# Trigger_And_Clock_Muxing.net
KiCad netlist of a schematic drawn in Altium Designer
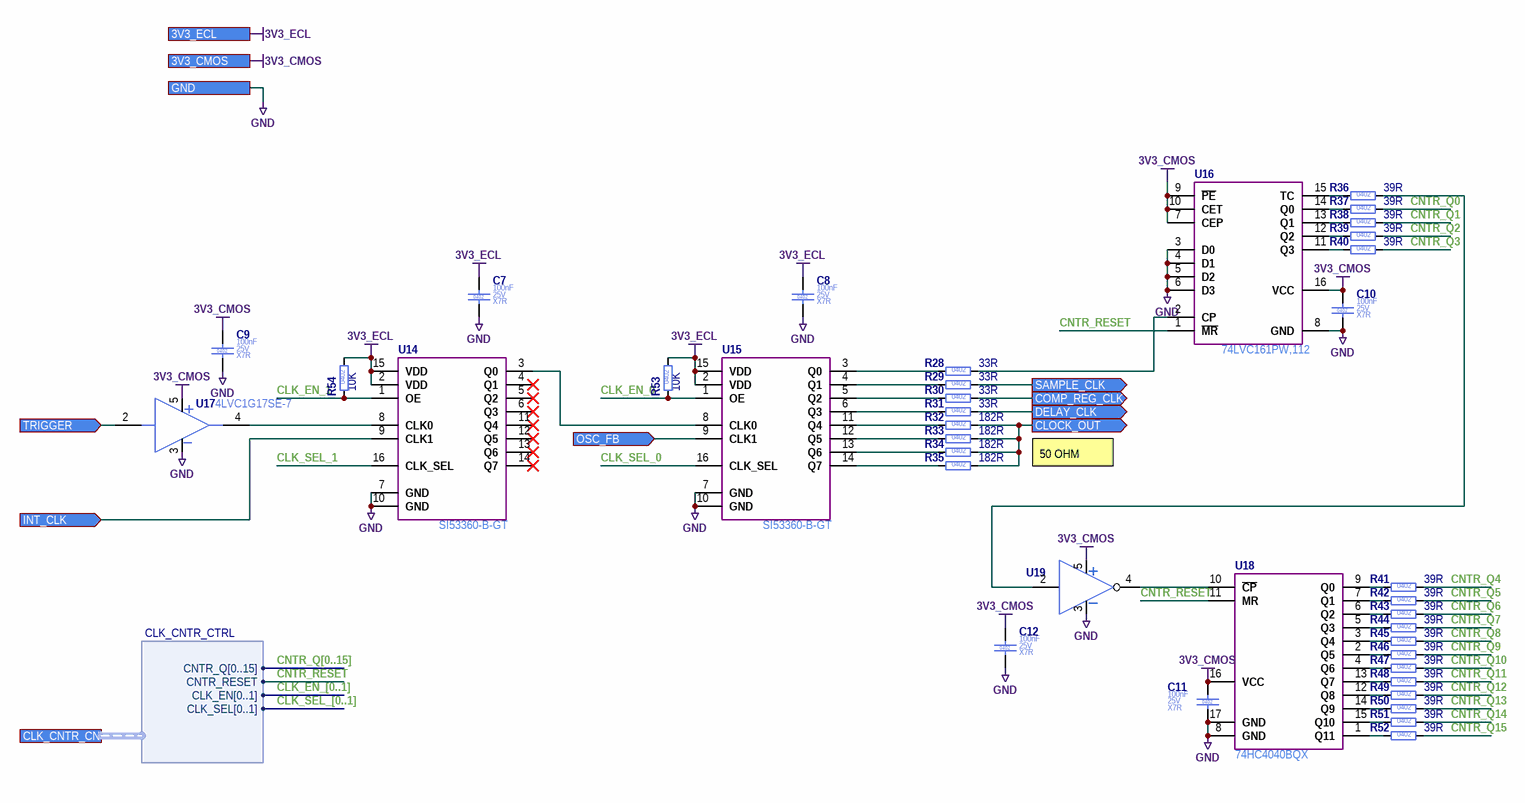
[diagram p0: Trigger_And_Clock_Muxing.SchDoc]

(export (version "E")
  (design (tool "Eeschema 10.0.6"))
  (components
    (comp (ref "C7")
      (value "C_100NF_25V_X7R_0402_10")
      (footprint "C_0402_1005")
      (description "Ceramic Capacitor")
      (fields
        (field (name "CASE/PACKAGE") "0402")
        (field (name "VOLTAGE RATING (DC)") "25V")
        (field (name "DIELECTRIC") "X7R")
        (field (name "CAPACITANCE") "100nF")
        (field (name "TOLERANCE") "10%")
        (field (name "MANUFACTURER PART NUMBER") "EMK105B7104KV-F")
      )
      (libsource (lib "7Sigma") (part "C"))
    )
    (comp (ref "C8")
      (value "C_100NF_25V_X7R_0402_10")
      (footprint "C_0402_1005")
      (description "Ceramic Capacitor")
      (fields
        (field (name "CASE/PACKAGE") "0402")
        (field (name "VOLTAGE RATING (DC)") "25V")
        (field (name "DIELECTRIC") "X7R")
        (field (name "CAPACITANCE") "100nF")
        (field (name "TOLERANCE") "10%")
        (field (name "MANUFACTURER PART NUMBER") "EMK105B7104KV-F")
      )
      (libsource (lib "7Sigma") (part "C"))
    )
    (comp (ref "C9")
      (value "C_100NF_25V_X7R_0402_10")
      (footprint "C_0402_1005")
      (description "Ceramic Capacitor")
      (fields
        (field (name "CASE/PACKAGE") "0402")
        (field (name "VOLTAGE RATING (DC)") "25V")
        (field (name "DIELECTRIC") "X7R")
        (field (name "CAPACITANCE") "100nF")
        (field (name "TOLERANCE") "10%")
        (field (name "MANUFACTURER PART NUMBER") "EMK105B7104KV-F")
      )
      (libsource (lib "7Sigma") (part "C"))
    )
    (comp (ref "C10")
      (value "C_100NF_25V_X7R_0402_10")
      (footprint "C_0402_1005")
      (description "Ceramic Capacitor")
      (fields
        (field (name "CASE/PACKAGE") "0402")
        (field (name "VOLTAGE RATING (DC)") "25V")
        (field (name "DIELECTRIC") "X7R")
        (field (name "CAPACITANCE") "100nF")
        (field (name "TOLERANCE") "10%")
        (field (name "MANUFACTURER PART NUMBER") "EMK105B7104KV-F")
      )
      (libsource (lib "7Sigma") (part "C"))
    )
    (comp (ref "C11")
      (value "C_100NF_25V_X7R_0402_10")
      (footprint "C_0402_1005")
      (description "Ceramic Capacitor")
      (fields
        (field (name "CASE/PACKAGE") "0402")
        (field (name "VOLTAGE RATING (DC)") "25V")
        (field (name "DIELECTRIC") "X7R")
        (field (name "CAPACITANCE") "100nF")
        (field (name "TOLERANCE") "10%")
        (field (name "MANUFACTURER PART NUMBER") "EMK105B7104KV-F")
      )
      (libsource (lib "7Sigma") (part "C"))
    )
    (comp (ref "C12")
      (value "C_100NF_25V_X7R_0402_10")
      (footprint "C_0402_1005")
      (description "Ceramic Capacitor")
      (fields
        (field (name "CASE/PACKAGE") "0402")
        (field (name "VOLTAGE RATING (DC)") "25V")
        (field (name "DIELECTRIC") "X7R")
        (field (name "CAPACITANCE") "100nF")
        (field (name "TOLERANCE") "10%")
        (field (name "MANUFACTURER PART NUMBER") "EMK105B7104KV-F")
      )
      (libsource (lib "7Sigma") (part "C"))
    )
    (comp (ref "R28")
      (value "R_33R_0402_1")
      (footprint "R_0402_1005")
      (description "Thick Film Resistor")
      (fields
        (field (name "RESISTANCE") "33R")
        (field (name "CASE/PACKAGE") "0402")
        (field (name "TOLERANCE") "1%")
        (field (name "MANUFACTURER") "Yageo")
      )
      (libsource (lib "7Sigma") (part "R"))
    )
    (comp (ref "R29")
      (value "R_33R_0402_1")
      (footprint "R_0402_1005")
      (description "Thick Film Resistor")
      (fields
        (field (name "RESISTANCE") "33R")
        (field (name "CASE/PACKAGE") "0402")
        (field (name "TOLERANCE") "1%")
        (field (name "MANUFACTURER") "Yageo")
      )
      (libsource (lib "7Sigma") (part "R"))
    )
    (comp (ref "R30")
      (value "R_33R_0402_1")
      (footprint "R_0402_1005")
      (description "Thick Film Resistor")
      (fields
        (field (name "RESISTANCE") "33R")
        (field (name "CASE/PACKAGE") "0402")
        (field (name "TOLERANCE") "1%")
        (field (name "MANUFACTURER") "Yageo")
      )
      (libsource (lib "7Sigma") (part "R"))
    )
    (comp (ref "R31")
      (value "R_33R_0402_1")
      (footprint "R_0402_1005")
      (description "Thick Film Resistor")
      (fields
        (field (name "RESISTANCE") "33R")
        (field (name "CASE/PACKAGE") "0402")
        (field (name "TOLERANCE") "1%")
        (field (name "MANUFACTURER") "Yageo")
      )
      (libsource (lib "7Sigma") (part "R"))
    )
    (comp (ref "R32")
      (value "R_182R_0402_1")
      (footprint "R_0402_1005")
      (description "Thick Film Resistor")
      (fields
        (field (name "RESISTANCE") "182R")
        (field (name "CASE/PACKAGE") "0402")
        (field (name "TOLERANCE") "1%")
        (field (name "MANUFACTURER") "Yageo")
      )
      (libsource (lib "7Sigma") (part "R"))
    )
    (comp (ref "R33")
      (value "R_182R_0402_1")
      (footprint "R_0402_1005")
      (description "Thick Film Resistor")
      (fields
        (field (name "RESISTANCE") "182R")
        (field (name "CASE/PACKAGE") "0402")
        (field (name "TOLERANCE") "1%")
        (field (name "MANUFACTURER") "Yageo")
      )
      (libsource (lib "7Sigma") (part "R"))
    )
    (comp (ref "R34")
      (value "R_182R_0402_1")
      (footprint "R_0402_1005")
      (description "Thick Film Resistor")
      (fields
        (field (name "RESISTANCE") "182R")
        (field (name "CASE/PACKAGE") "0402")
        (field (name "TOLERANCE") "1%")
        (field (name "MANUFACTURER") "Yageo")
      )
      (libsource (lib "7Sigma") (part "R"))
    )
    (comp (ref "R35")
      (value "R_182R_0402_1")
      (footprint "R_0402_1005")
      (description "Thick Film Resistor")
      (fields
        (field (name "RESISTANCE") "182R")
        (field (name "CASE/PACKAGE") "0402")
        (field (name "TOLERANCE") "1%")
        (field (name "MANUFACTURER") "Yageo")
      )
      (libsource (lib "7Sigma") (part "R"))
    )
    (comp (ref "R36")
      (value "R_39R_0402_1")
      (footprint "R_0402_1005")
      (description "Thick Film Resistor")
      (fields
        (field (name "RESISTANCE") "39R")
        (field (name "CASE/PACKAGE") "0402")
        (field (name "TOLERANCE") "1%")
        (field (name "MANUFACTURER") "Yageo")
      )
      (libsource (lib "7Sigma") (part "R"))
    )
    (comp (ref "R37")
      (value "R_39R_0402_1")
      (footprint "R_0402_1005")
      (description "Thick Film Resistor")
      (fields
        (field (name "RESISTANCE") "39R")
        (field (name "CASE/PACKAGE") "0402")
        (field (name "TOLERANCE") "1%")
        (field (name "MANUFACTURER") "Yageo")
      )
      (libsource (lib "7Sigma") (part "R"))
    )
    (comp (ref "R38")
      (value "R_39R_0402_1")
      (footprint "R_0402_1005")
      (description "Thick Film Resistor")
      (fields
        (field (name "RESISTANCE") "39R")
        (field (name "CASE/PACKAGE") "0402")
        (field (name "TOLERANCE") "1%")
        (field (name "MANUFACTURER") "Yageo")
      )
      (libsource (lib "7Sigma") (part "R"))
    )
    (comp (ref "R39")
      (value "R_39R_0402_1")
      (footprint "R_0402_1005")
      (description "Thick Film Resistor")
      (fields
        (field (name "RESISTANCE") "39R")
        (field (name "CASE/PACKAGE") "0402")
        (field (name "TOLERANCE") "1%")
        (field (name "MANUFACTURER") "Yageo")
      )
      (libsource (lib "7Sigma") (part "R"))
    )
    (comp (ref "R40")
      (value "R_39R_0402_1")
      (footprint "R_0402_1005")
      (description "Thick Film Resistor")
      (fields
        (field (name "RESISTANCE") "39R")
        (field (name "CASE/PACKAGE") "0402")
        (field (name "TOLERANCE") "1%")
        (field (name "MANUFACTURER") "Yageo")
      )
      (libsource (lib "7Sigma") (part "R"))
    )
    (comp (ref "R41")
      (value "R_39R_0402_1")
      (footprint "R_0402_1005")
      (description "Thick Film Resistor")
      (fields
        (field (name "RESISTANCE") "39R")
        (field (name "CASE/PACKAGE") "0402")
        (field (name "TOLERANCE") "1%")
        (field (name "MANUFACTURER") "Yageo")
      )
      (libsource (lib "7Sigma") (part "R"))
    )
    (comp (ref "R42")
      (value "R_39R_0402_1")
      (footprint "R_0402_1005")
      (description "Thick Film Resistor")
      (fields
        (field (name "RESISTANCE") "39R")
        (field (name "CASE/PACKAGE") "0402")
        (field (name "TOLERANCE") "1%")
        (field (name "MANUFACTURER") "Yageo")
      )
      (libsource (lib "7Sigma") (part "R"))
    )
    (comp (ref "R43")
      (value "R_39R_0402_1")
      (footprint "R_0402_1005")
      (description "Thick Film Resistor")
      (fields
        (field (name "RESISTANCE") "39R")
        (field (name "CASE/PACKAGE") "0402")
        (field (name "TOLERANCE") "1%")
        (field (name "MANUFACTURER") "Yageo")
      )
      (libsource (lib "7Sigma") (part "R"))
    )
    (comp (ref "R44")
      (value "R_39R_0402_1")
      (footprint "R_0402_1005")
      (description "Thick Film Resistor")
      (fields
        (field (name "RESISTANCE") "39R")
        (field (name "CASE/PACKAGE") "0402")
        (field (name "TOLERANCE") "1%")
        (field (name "MANUFACTURER") "Yageo")
      )
      (libsource (lib "7Sigma") (part "R"))
    )
    (comp (ref "R45")
      (value "R_39R_0402_1")
      (footprint "R_0402_1005")
      (description "Thick Film Resistor")
      (fields
        (field (name "RESISTANCE") "39R")
        (field (name "CASE/PACKAGE") "0402")
        (field (name "TOLERANCE") "1%")
        (field (name "MANUFACTURER") "Yageo")
      )
      (libsource (lib "7Sigma") (part "R"))
    )
    (comp (ref "R46")
      (value "R_39R_0402_1")
      (footprint "R_0402_1005")
      (description "Thick Film Resistor")
      (fields
        (field (name "RESISTANCE") "39R")
        (field (name "CASE/PACKAGE") "0402")
        (field (name "TOLERANCE") "1%")
        (field (name "MANUFACTURER") "Yageo")
      )
      (libsource (lib "7Sigma") (part "R"))
    )
    (comp (ref "R47")
      (value "R_39R_0402_1")
      (footprint "R_0402_1005")
      (description "Thick Film Resistor")
      (fields
        (field (name "RESISTANCE") "39R")
        (field (name "CASE/PACKAGE") "0402")
        (field (name "TOLERANCE") "1%")
        (field (name "MANUFACTURER") "Yageo")
      )
      (libsource (lib "7Sigma") (part "R"))
    )
    (comp (ref "R48")
      (value "R_39R_0402_1")
      (footprint "R_0402_1005")
      (description "Thick Film Resistor")
      (fields
        (field (name "RESISTANCE") "39R")
        (field (name "CASE/PACKAGE") "0402")
        (field (name "TOLERANCE") "1%")
        (field (name "MANUFACTURER") "Yageo")
      )
      (libsource (lib "7Sigma") (part "R"))
    )
    (comp (ref "R49")
      (value "R_39R_0402_1")
      (footprint "R_0402_1005")
      (description "Thick Film Resistor")
      (fields
        (field (name "RESISTANCE") "39R")
        (field (name "CASE/PACKAGE") "0402")
        (field (name "TOLERANCE") "1%")
        (field (name "MANUFACTURER") "Yageo")
      )
      (libsource (lib "7Sigma") (part "R"))
    )
    (comp (ref "R50")
      (value "R_39R_0402_1")
      (footprint "R_0402_1005")
      (description "Thick Film Resistor")
      (fields
        (field (name "RESISTANCE") "39R")
        (field (name "CASE/PACKAGE") "0402")
        (field (name "TOLERANCE") "1%")
        (field (name "MANUFACTURER") "Yageo")
      )
      (libsource (lib "7Sigma") (part "R"))
    )
    (comp (ref "R51")
      (value "R_39R_0402_1")
      (footprint "R_0402_1005")
      (description "Thick Film Resistor")
      (fields
        (field (name "RESISTANCE") "39R")
        (field (name "CASE/PACKAGE") "0402")
        (field (name "TOLERANCE") "1%")
        (field (name "MANUFACTURER") "Yageo")
      )
      (libsource (lib "7Sigma") (part "R"))
    )
    (comp (ref "R52")
      (value "R_39R_0402_1")
      (footprint "R_0402_1005")
      (description "Thick Film Resistor")
      (fields
        (field (name "RESISTANCE") "39R")
        (field (name "CASE/PACKAGE") "0402")
        (field (name "TOLERANCE") "1%")
        (field (name "MANUFACTURER") "Yageo")
      )
      (libsource (lib "7Sigma") (part "R"))
    )
    (comp (ref "R53")
      (value "R_10K_0402_1")
      (footprint "R_0402_1005")
      (description "Thick Film Resistor")
      (fields
        (field (name "RESISTANCE") "10K")
        (field (name "CASE/PACKAGE") "0402")
        (field (name "TOLERANCE") "1%")
        (field (name "MANUFACTURER") "Yageo")
      )
      (libsource (lib "7Sigma") (part "R"))
    )
    (comp (ref "R54")
      (value "R_10K_0402_1")
      (footprint "R_0402_1005")
      (description "Thick Film Resistor")
      (fields
        (field (name "RESISTANCE") "10K")
        (field (name "CASE/PACKAGE") "0402")
        (field (name "TOLERANCE") "1%")
        (field (name "MANUFACTURER") "Yageo")
      )
      (libsource (lib "7Sigma") (part "R"))
    )
    (comp (ref "U14")
      (value "Si53360-B-GT")
      (footprint "TSOP65P640X120-16N")
      (description "Low Jitter Clock Buffer")
      (fields
        (field (name "MANUFACTURER") "Silicon Labs")
        (field (name "MANUFACTURER PART NUMBER") "SI53360-B-GT")
      )
      (libsource (lib "7Sigma") (part "Si53360-B-GT"))
    )
    (comp (ref "U15")
      (value "Si53360-B-GT")
      (footprint "TSOP65P640X120-16N")
      (description "Low Jitter Clock Buffer")
      (fields
        (field (name "MANUFACTURER") "Silicon Labs")
        (field (name "MANUFACTURER PART NUMBER") "SI53360-B-GT")
      )
      (libsource (lib "7Sigma") (part "Si53360-B-GT"))
    )
    (comp (ref "U16")
      (value "74LVC161PW,112")
      (footprint "TSOP65P640X120-16N")
      (description "4 bit Counter with preset")
      (fields
        (field (name "MANUFACTURER") "Nexperia")
        (field (name "MANUFACTURER PART NUMBER") "74LVC161PW,112")
      )
      (libsource (lib "7Sigma") (part "74LVC161PW"))
    )
    (comp (ref "U17")
      (value "74LVC1G17SE-7")
      (footprint "SC70-5_SOT353_TSSOP5")
      (description "Schmitt Buffer")
      (fields
        (field (name "MANUFACTURER PART NUMBER") "74LVC1G17SE-7")
        (field (name "MANUFACTURER") "Diodes Incorporated")
      )
      (libsource (lib "7Sigma") (part "74LVC1G17SE-7"))
    )
    (comp (ref "U18")
      (value "74HC4040BQX")
      (footprint "QFN50P350X250X100_HS-17N")
      (description "12 bit binary ripple counter")
      (fields
        (field (name "MANUFACTURER PART NUMBER") "74HC4040BQX")
        (field (name "MANUFACTURER") "Nexperia")
      )
      (libsource (lib "7Sigma") (part "74HC4040BQX"))
    )
    (comp (ref "U19")
      (value "SN74AHC1G04DBVR")
      (footprint "SOT23-5_SC74A_SOT753_M")
      (description "Inverters Single")
      (fields (field (name "MANUFACTURER") "Texas Instruments"))
      (libsource (lib "7Sigma") (part "SN74AHC1G04DBVR"))
    )
  )
  (nets
    (net (code "2") (name "/CLK_EN_0") (class "Default")
      (node (ref "R53") (pin "1") (pinfunction "1_1") (pintype "passive"))
      (node (ref "U15") (pin "1") (pinfunction "OE_1") (pintype "passive"))
    )
    (net (code "3") (name "/CLK_EN_1") (class "Default")
      (node (ref "R54") (pin "1") (pinfunction "1_1") (pintype "passive"))
      (node (ref "U14") (pin "1") (pinfunction "OE_1") (pintype "passive"))
    )
    (net (code "5") (name "/CLK_SEL_0") (class "Default")
      (node (ref "U15") (pin "16") (pinfunction "CLK_SEL_16") (pintype "passive"))
    )
    (net (code "6") (name "/CLK_SEL_1") (class "Default")
      (node (ref "U14") (pin "16") (pinfunction "CLK_SEL_16") (pintype "passive"))
    )
    (net (code "8") (name "/CLOCK_OUT") (class "Default")
      (node (ref "R32") (pin "2") (pinfunction "2_2") (pintype "passive"))
      (node (ref "R33") (pin "2") (pinfunction "2_2") (pintype "passive"))
      (node (ref "R34") (pin "2") (pinfunction "2_2") (pintype "passive"))
      (node (ref "R35") (pin "2") (pinfunction "2_2") (pintype "passive"))
    )
    (net (code "9") (name "/CNTR_Q0") (class "Default")
      (node (ref "R37") (pin "2") (pinfunction "2_2") (pintype "passive"))
    )
    (net (code "10") (name "/CNTR_Q1") (class "Default")
      (node (ref "R38") (pin "2") (pinfunction "2_2") (pintype "passive"))
    )
    (net (code "11") (name "/CNTR_Q2") (class "Default")
      (node (ref "R39") (pin "2") (pinfunction "2_2") (pintype "passive"))
    )
    (net (code "12") (name "/CNTR_Q3") (class "Default")
      (node (ref "R40") (pin "2") (pinfunction "2_2") (pintype "passive"))
    )
    (net (code "13") (name "/CNTR_Q4") (class "Default")
      (node (ref "R41") (pin "2") (pinfunction "2_2") (pintype "passive"))
    )
    (net (code "14") (name "/CNTR_Q5") (class "Default")
      (node (ref "R42") (pin "2") (pinfunction "2_2") (pintype "passive"))
    )
    (net (code "15") (name "/CNTR_Q6") (class "Default")
      (node (ref "R43") (pin "2") (pinfunction "2_2") (pintype "passive"))
    )
    (net (code "16") (name "/CNTR_Q7") (class "Default")
      (node (ref "R44") (pin "2") (pinfunction "2_2") (pintype "passive"))
    )
    (net (code "17") (name "/CNTR_Q8") (class "Default")
      (node (ref "R45") (pin "2") (pinfunction "2_2") (pintype "passive"))
    )
    (net (code "18") (name "/CNTR_Q9") (class "Default")
      (node (ref "R46") (pin "2") (pinfunction "2_2") (pintype "passive"))
    )
    (net (code "19") (name "/CNTR_Q10") (class "Default")
      (node (ref "R47") (pin "2") (pinfunction "2_2") (pintype "passive"))
    )
    (net (code "20") (name "/CNTR_Q11") (class "Default")
      (node (ref "R48") (pin "2") (pinfunction "2_2") (pintype "passive"))
    )
    (net (code "21") (name "/CNTR_Q12") (class "Default")
      (node (ref "R49") (pin "2") (pinfunction "2_2") (pintype "passive"))
    )
    (net (code "22") (name "/CNTR_Q13") (class "Default")
      (node (ref "R50") (pin "2") (pinfunction "2_2") (pintype "passive"))
    )
    (net (code "23") (name "/CNTR_Q14") (class "Default")
      (node (ref "R51") (pin "2") (pinfunction "2_2") (pintype "passive"))
    )
    (net (code "24") (name "/CNTR_Q15") (class "Default")
      (node (ref "R52") (pin "2") (pinfunction "2_2") (pintype "passive"))
    )
    (net (code "26") (name "/CNTR_RESET") (class "Default")
      (node (ref "U16") (pin "1") (pinfunction "MR_1") (pintype "passive"))
      (node (ref "U18") (pin "11") (pinfunction "MR_11") (pintype "passive"))
    )
    (net (code "27") (name "/COMP_REG_CLK") (class "Default")
      (node (ref "R30") (pin "2") (pinfunction "2_2") (pintype "passive"))
    )
    (net (code "28") (name "/DELAY_CLK") (class "Default")
      (node (ref "R31") (pin "2") (pinfunction "2_2") (pintype "passive"))
    )
    (net (code "29") (name "/INT_CLK") (class "Default")
      (node (ref "U14") (pin "9") (pinfunction "CLK1_9") (pintype "passive"))
    )
    (net (code "30") (name "/OSC_FB") (class "Default")
      (node (ref "U15") (pin "9") (pinfunction "CLK1_9") (pintype "passive"))
    )
    (net (code "31") (name "/SAMPLE_CLK") (class "Default")
      (node (ref "R29") (pin "2") (pinfunction "2_2") (pintype "passive"))
    )
    (net (code "32") (name "/TRIGGER") (class "Default")
      (node (ref "U17") (pin "2") (pinfunction "A_2") (pintype "passive"))
    )
    (net (code "34") (name "3V3_CMOS") (class "Default")
      (node (ref "C10") (pin "1") (pinfunction "1_1") (pintype "passive"))
      (node (ref "C11") (pin "1") (pinfunction "1_1") (pintype "passive"))
      (node (ref "C12") (pin "1") (pinfunction "1_1") (pintype "passive"))
      (node (ref "C9") (pin "1") (pinfunction "1_1") (pintype "passive"))
      (node (ref "U16") (pin "10") (pinfunction "CET_10") (pintype "passive"))
      (node (ref "U16") (pin "16") (pinfunction "VCC_16") (pintype "passive"))
      (node (ref "U16") (pin "7") (pinfunction "CEP_7") (pintype "passive"))
      (node (ref "U16") (pin "9") (pinfunction "PE_9") (pintype "passive"))
      (node (ref "U17") (pin "5") (pinfunction "VCC_5") (pintype "passive"))
      (node (ref "U18") (pin "16") (pinfunction "VCC_16") (pintype "passive"))
      (node (ref "U19") (pin "5") (pinfunction "VCC_5") (pintype "passive"))
    )
    (net (code "35") (name "3V3_ECL") (class "Default")
      (node (ref "C7") (pin "1") (pinfunction "1_1") (pintype "passive"))
      (node (ref "C8") (pin "1") (pinfunction "1_1") (pintype "passive"))
      (node (ref "R53") (pin "2") (pinfunction "2_2") (pintype "passive"))
      (node (ref "R54") (pin "2") (pinfunction "2_2") (pintype "passive"))
      (node (ref "U14") (pin "15") (pinfunction "VDD_15") (pintype "passive"))
      (node (ref "U14") (pin "2") (pinfunction "VDD_2") (pintype "passive"))
      (node (ref "U15") (pin "15") (pinfunction "VDD_15") (pintype "passive"))
      (node (ref "U15") (pin "2") (pinfunction "VDD_2") (pintype "passive"))
    )
    (net (code "36") (name "GND") (class "Default")
      (node (ref "C10") (pin "2") (pinfunction "2_2") (pintype "passive"))
      (node (ref "C11") (pin "2") (pinfunction "2_2") (pintype "passive"))
      (node (ref "C12") (pin "2") (pinfunction "2_2") (pintype "passive"))
      (node (ref "C7") (pin "2") (pinfunction "2_2") (pintype "passive"))
      (node (ref "C8") (pin "2") (pinfunction "2_2") (pintype "passive"))
      (node (ref "C9") (pin "2") (pinfunction "2_2") (pintype "passive"))
      (node (ref "U14") (pin "10") (pinfunction "GND_10") (pintype "passive"))
      (node (ref "U14") (pin "7") (pinfunction "GND_7") (pintype "passive"))
      (node (ref "U15") (pin "10") (pinfunction "GND_10") (pintype "passive"))
      (node (ref "U15") (pin "7") (pinfunction "GND_7") (pintype "passive"))
      (node (ref "U16") (pin "3") (pinfunction "D0_3") (pintype "passive"))
      (node (ref "U16") (pin "4") (pinfunction "D1_4") (pintype "passive"))
      (node (ref "U16") (pin "5") (pinfunction "D2_5") (pintype "passive"))
      (node (ref "U16") (pin "6") (pinfunction "D3_6") (pintype "passive"))
      (node (ref "U16") (pin "8") (pinfunction "GND_8") (pintype "passive"))
      (node (ref "U17") (pin "3") (pinfunction "GND_3") (pintype "passive"))
      (node (ref "U18") (pin "17") (pinfunction "GND_17") (pintype "passive"))
      (node (ref "U18") (pin "8") (pinfunction "GND_8") (pintype "passive"))
      (node (ref "U19") (pin "3") (pinfunction "GND_3") (pintype "passive"))
    )
    (net (code "37") (name "Net-(R36-Pad2)") (class "Default")
      (node (ref "R36") (pin "2") (pinfunction "2_2") (pintype "passive"))
      (node (ref "U19") (pin "2") (pinfunction "2_2") (pintype "passive"))
    )
    (net (code "38") (name "Net-(U14-CLK0)") (class "Default")
      (node (ref "U14") (pin "8") (pinfunction "CLK0_8") (pintype "passive"))
      (node (ref "U17") (pin "4") (pinfunction "Y_4") (pintype "passive"))
    )
    (net (code "39") (name "Net-(U14-Q0)") (class "Default")
      (node (ref "U14") (pin "3") (pinfunction "Q0_3") (pintype "passive"))
      (node (ref "U15") (pin "8") (pinfunction "CLK0_8") (pintype "passive"))
    )
    (net (code "40") (name "Net-(U15-Q0)") (class "Default")
      (node (ref "R28") (pin "1") (pinfunction "1_1") (pintype "passive"))
      (node (ref "U15") (pin "3") (pinfunction "Q0_3") (pintype "passive"))
    )
    (net (code "41") (name "Net-(U15-Q1)") (class "Default")
      (node (ref "R29") (pin "1") (pinfunction "1_1") (pintype "passive"))
      (node (ref "U15") (pin "4") (pinfunction "Q1_4") (pintype "passive"))
    )
    (net (code "42") (name "Net-(U15-Q2)") (class "Default")
      (node (ref "R30") (pin "1") (pinfunction "1_1") (pintype "passive"))
      (node (ref "U15") (pin "5") (pinfunction "Q2_5") (pintype "passive"))
    )
    (net (code "43") (name "Net-(U15-Q3)") (class "Default")
      (node (ref "R31") (pin "1") (pinfunction "1_1") (pintype "passive"))
      (node (ref "U15") (pin "6") (pinfunction "Q3_6") (pintype "passive"))
    )
    (net (code "44") (name "Net-(U15-Q4)") (class "Default")
      (node (ref "R32") (pin "1") (pinfunction "1_1") (pintype "passive"))
      (node (ref "U15") (pin "11") (pinfunction "Q4_11") (pintype "passive"))
    )
    (net (code "45") (name "Net-(U15-Q5)") (class "Default")
      (node (ref "R33") (pin "1") (pinfunction "1_1") (pintype "passive"))
      (node (ref "U15") (pin "12") (pinfunction "Q5_12") (pintype "passive"))
    )
    (net (code "46") (name "Net-(U15-Q6)") (class "Default")
      (node (ref "R34") (pin "1") (pinfunction "1_1") (pintype "passive"))
      (node (ref "U15") (pin "13") (pinfunction "Q6_13") (pintype "passive"))
    )
    (net (code "47") (name "Net-(U15-Q7)") (class "Default")
      (node (ref "R35") (pin "1") (pinfunction "1_1") (pintype "passive"))
      (node (ref "U15") (pin "14") (pinfunction "Q7_14") (pintype "passive"))
    )
    (net (code "48") (name "Net-(U16-CP)") (class "Default")
      (node (ref "R28") (pin "2") (pinfunction "2_2") (pintype "passive"))
      (node (ref "U16") (pin "2") (pinfunction "CP_2") (pintype "passive"))
    )
    (net (code "49") (name "Net-(U16-Q0)") (class "Default")
      (node (ref "R37") (pin "1") (pinfunction "1_1") (pintype "passive"))
      (node (ref "U16") (pin "14") (pinfunction "Q0_14") (pintype "passive"))
    )
    (net (code "50") (name "Net-(U16-Q1)") (class "Default")
      (node (ref "R38") (pin "1") (pinfunction "1_1") (pintype "passive"))
      (node (ref "U16") (pin "13") (pinfunction "Q1_13") (pintype "passive"))
    )
    (net (code "51") (name "Net-(U16-Q2)") (class "Default")
      (node (ref "R39") (pin "1") (pinfunction "1_1") (pintype "passive"))
      (node (ref "U16") (pin "12") (pinfunction "Q2_12") (pintype "passive"))
    )
    (net (code "52") (name "Net-(U16-Q3)") (class "Default")
      (node (ref "R40") (pin "1") (pinfunction "1_1") (pintype "passive"))
      (node (ref "U16") (pin "11") (pinfunction "Q3_11") (pintype "passive"))
    )
    (net (code "53") (name "Net-(U16-TC)") (class "Default")
      (node (ref "R36") (pin "1") (pinfunction "1_1") (pintype "passive"))
      (node (ref "U16") (pin "15") (pinfunction "TC_15") (pintype "passive"))
    )
    (net (code "54") (name "Net-(U18-CP)") (class "Default")
      (node (ref "U18") (pin "10") (pinfunction "CP_10") (pintype "passive"))
      (node (ref "U19") (pin "4") (pinfunction "OutY_4") (pintype "passive"))
    )
    (net (code "55") (name "Net-(U18-Q0)") (class "Default")
      (node (ref "R41") (pin "1") (pinfunction "1_1") (pintype "passive"))
      (node (ref "U18") (pin "9") (pinfunction "Q0_9") (pintype "passive"))
    )
    (net (code "56") (name "Net-(U18-Q1)") (class "Default")
      (node (ref "R42") (pin "1") (pinfunction "1_1") (pintype "passive"))
      (node (ref "U18") (pin "7") (pinfunction "Q1_7") (pintype "passive"))
    )
    (net (code "57") (name "Net-(U18-Q2)") (class "Default")
      (node (ref "R43") (pin "1") (pinfunction "1_1") (pintype "passive"))
      (node (ref "U18") (pin "6") (pinfunction "Q2_6") (pintype "passive"))
    )
    (net (code "58") (name "Net-(U18-Q3)") (class "Default")
      (node (ref "R44") (pin "1") (pinfunction "1_1") (pintype "passive"))
      (node (ref "U18") (pin "5") (pinfunction "Q3_5") (pintype "passive"))
    )
    (net (code "59") (name "Net-(U18-Q4)_1") (class "Default")
      (node (ref "R45") (pin "1") (pinfunction "1_1") (pintype "passive"))
      (node (ref "U18") (pin "3") (pinfunction "Q4_3") (pintype "passive"))
    )
    (net (code "60") (name "Net-(U18-Q5)") (class "Default")
      (node (ref "R46") (pin "1") (pinfunction "1_1") (pintype "passive"))
      (node (ref "U18") (pin "2") (pinfunction "Q5_2") (pintype "passive"))
    )
    (net (code "61") (name "Net-(U18-Q6)") (class "Default")
      (node (ref "R47") (pin "1") (pinfunction "1_1") (pintype "passive"))
      (node (ref "U18") (pin "4") (pinfunction "Q6_4") (pintype "passive"))
    )
    (net (code "62") (name "Net-(U18-Q7)") (class "Default")
      (node (ref "R48") (pin "1") (pinfunction "1_1") (pintype "passive"))
      (node (ref "U18") (pin "13") (pinfunction "Q7_13") (pintype "passive"))
    )
    (net (code "63") (name "Net-(U18-Q8)") (class "Default")
      (node (ref "R49") (pin "1") (pinfunction "1_1") (pintype "passive"))
      (node (ref "U18") (pin "12") (pinfunction "Q8_12") (pintype "passive"))
    )
    (net (code "64") (name "Net-(U18-Q9)") (class "Default")
      (node (ref "R50") (pin "1") (pinfunction "1_1") (pintype "passive"))
      (node (ref "U18") (pin "14") (pinfunction "Q9_14") (pintype "passive"))
    )
    (net (code "65") (name "Net-(U18-Q10)") (class "Default")
      (node (ref "R51") (pin "1") (pinfunction "1_1") (pintype "passive"))
      (node (ref "U18") (pin "15") (pinfunction "Q10_15") (pintype "passive"))
    )
    (net (code "66") (name "Net-(U18-Q11)") (class "Default")
      (node (ref "R52") (pin "1") (pinfunction "1_1") (pintype "passive"))
      (node (ref "U18") (pin "1") (pinfunction "Q11_1") (pintype "passive"))
    )
    (net (code "67") (name "unconnected-(U14-Q1-Pad4)") (class "Default")
      (node (ref "U14") (pin "4") (pinfunction "Q1_4") (pintype "passive+no_connect"))
    )
    (net (code "68") (name "unconnected-(U14-Q2-Pad5)") (class "Default")
      (node (ref "U14") (pin "5") (pinfunction "Q2_5") (pintype "passive+no_connect"))
    )
    (net (code "69") (name "unconnected-(U14-Q3-Pad6)") (class "Default")
      (node (ref "U14") (pin "6") (pinfunction "Q3_6") (pintype "passive+no_connect"))
    )
    (net (code "70") (name "unconnected-(U14-Q4-Pad11)") (class "Default")
      (node (ref "U14") (pin "11") (pinfunction "Q4_11") (pintype "passive+no_connect"))
    )
    (net (code "71") (name "unconnected-(U14-Q5-Pad12)") (class "Default")
      (node (ref "U14") (pin "12") (pinfunction "Q5_12") (pintype "passive+no_connect"))
    )
    (net (code "72") (name "unconnected-(U14-Q6-Pad13)") (class "Default")
      (node (ref "U14") (pin "13") (pinfunction "Q6_13") (pintype "passive+no_connect"))
    )
    (net (code "73") (name "unconnected-(U14-Q7-Pad14)") (class "Default")
      (node (ref "U14") (pin "14") (pinfunction "Q7_14") (pintype "passive+no_connect"))
    )
    (net (code "74") (name "unconnected-(U18-Q4-Pad3)") (class "Default")
      (node (ref "U18") (pin "3") (pinfunction "Q4_3") (pintype "input"))
    )
    (net (code "75") (name "unconnected-(U19-NC-Pad1)") (class "Default")
      (node (ref "U19") (pin "1") (pinfunction "NC_1") (pintype "passive"))
    )
  )
)
